# ArduinoZeroV4_0_1.net
KiCad netlist of a schematic drawn in Altium Designer
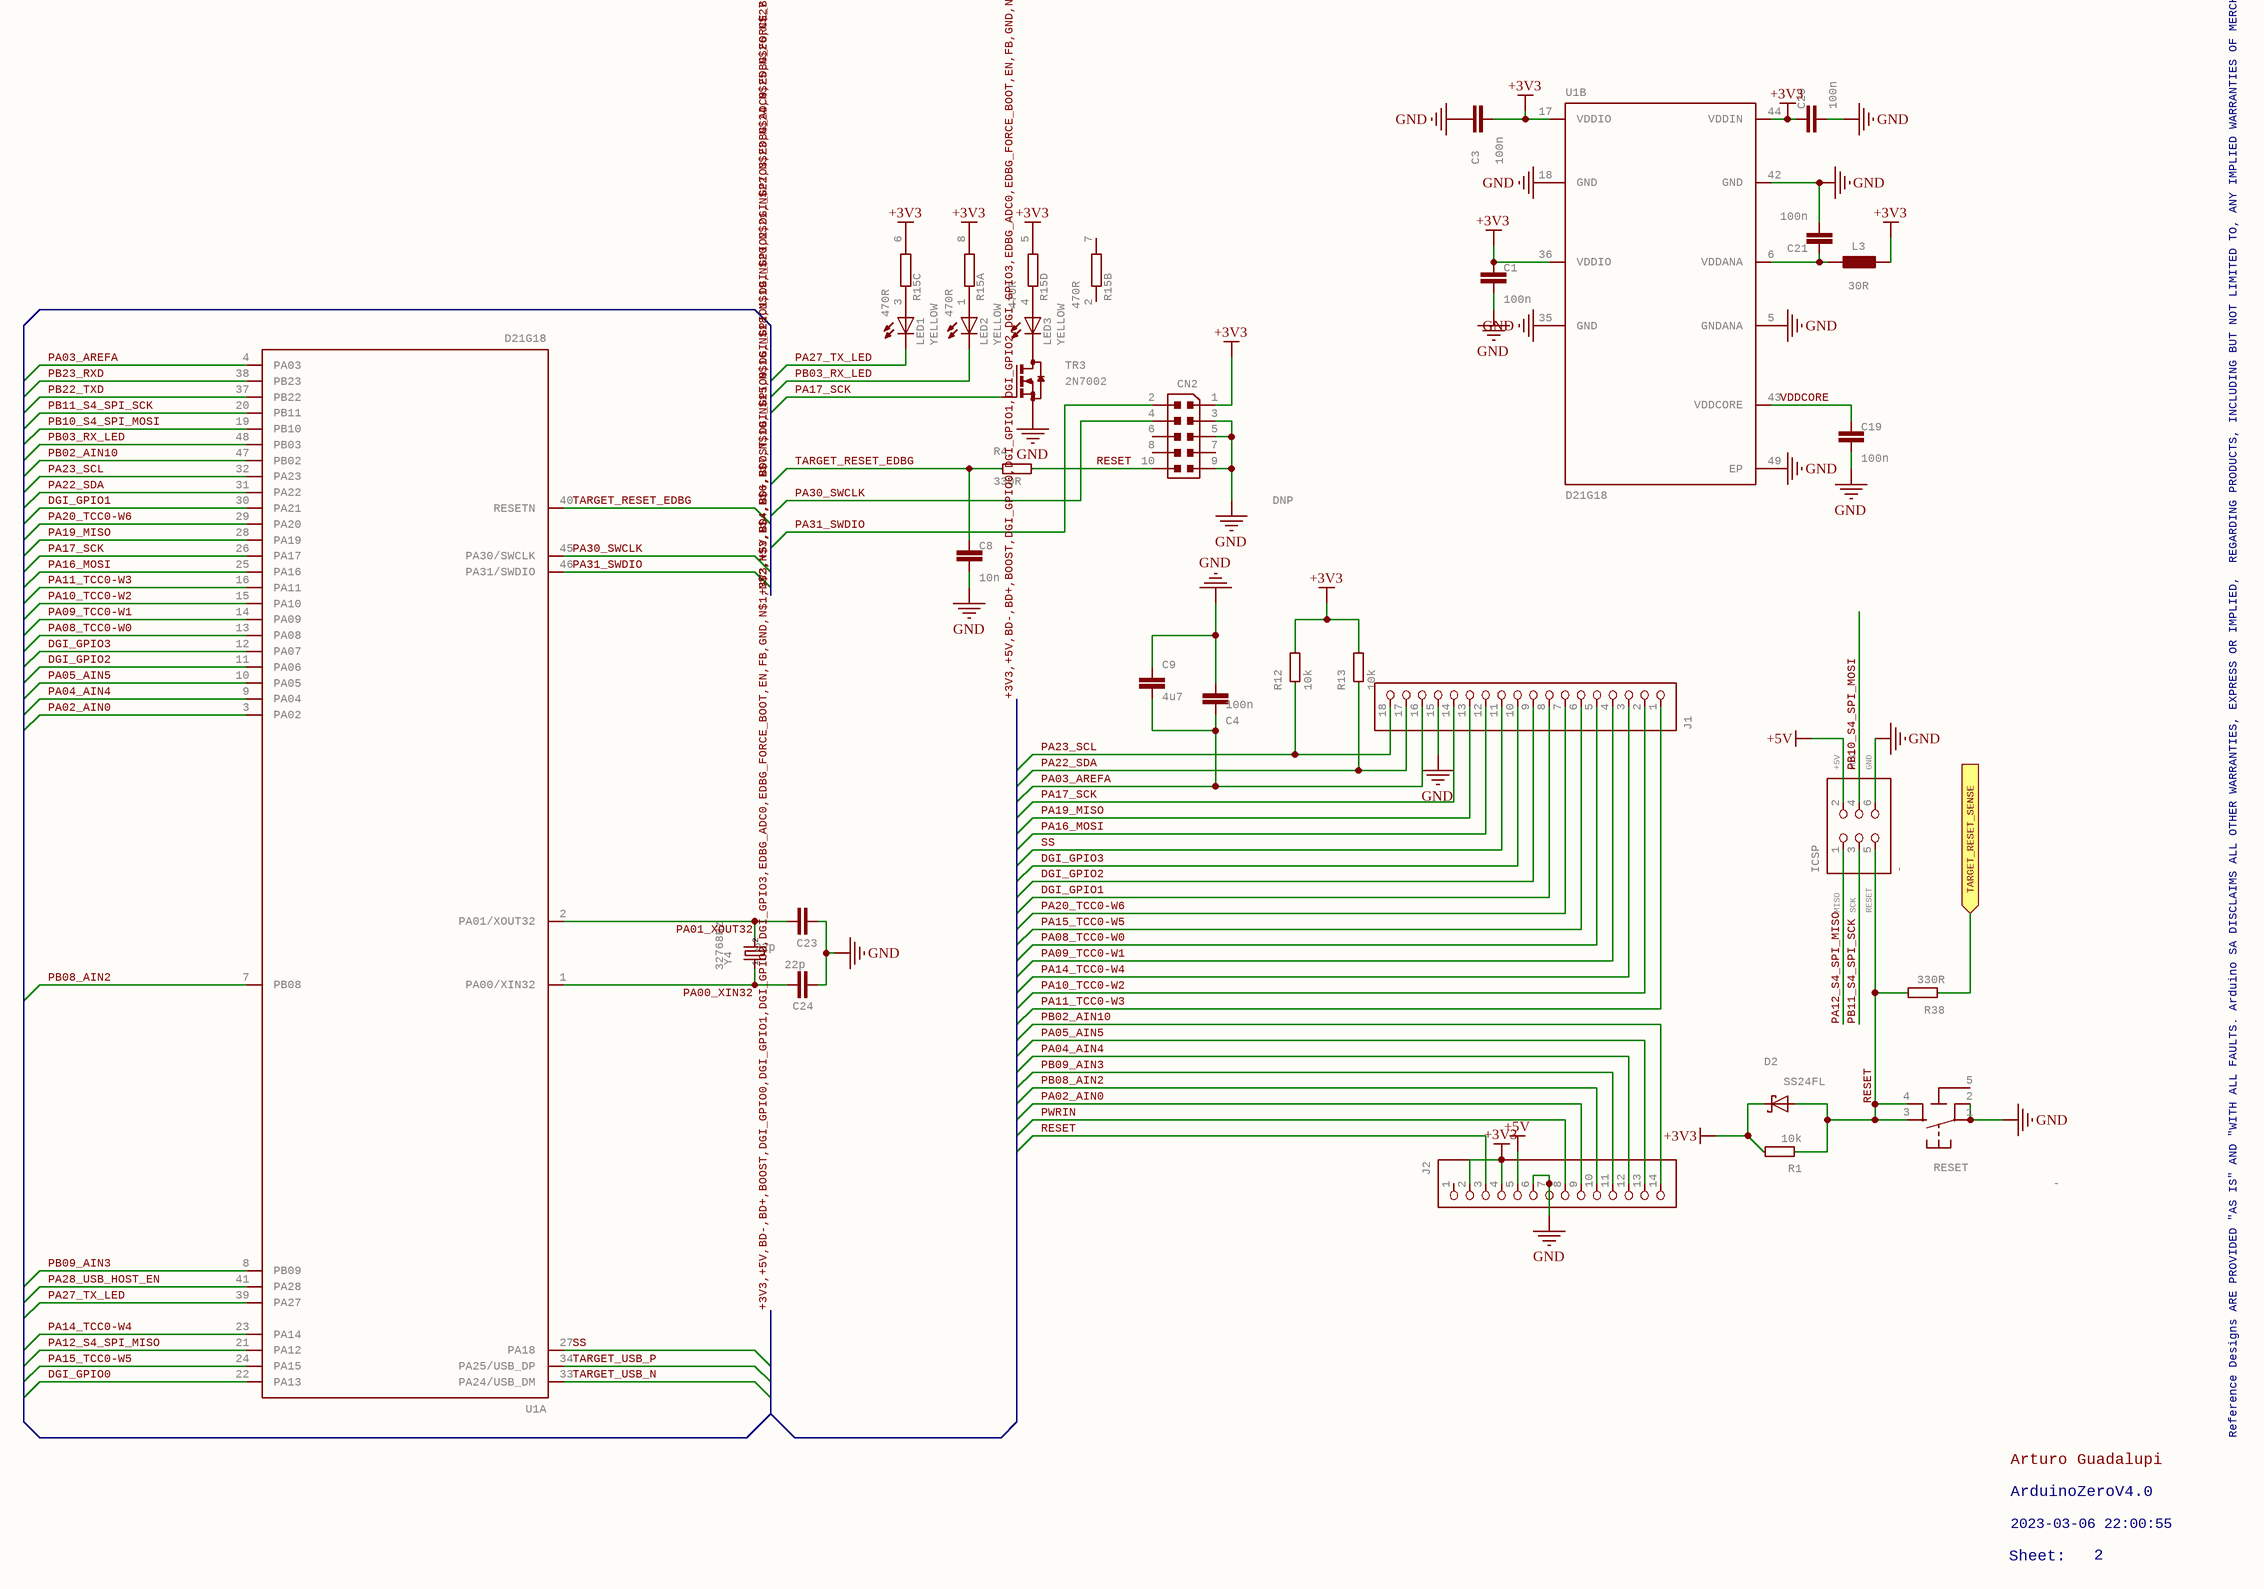
[diagram p0: ArduinoZeroV4.0_1.SchDoc]

(export (version "E")
  (design (tool "Eeschema 10.0.6"))
  (components
    (comp (ref "C1")
      (value "100n")
      (footprint "0603-1608X90N")
      (description "SMD Capacitor")
      (fields (field (name "MANUFACTURER") "Murata"))
      (libsource (lib "") (part "C-0603_1"))
    )
    (comp (ref "C3")
      (value "100n")
      (footprint "0603-1608X90N")
      (description "SMD Capacitor")
      (fields (field (name "MANUFACTURER") "Murata"))
      (libsource (lib "Arduino-rcl") (part "C-0603"))
    )
    (comp (ref "C4")
      (value "100n")
      (footprint "0402-1005X55N")
      (description "SMD Capacitor")
      (fields (field (name "MANUFACTURER") "TDK"))
      (libsource (lib "Arduino-rcl") (part "C-0402"))
    )
    (comp (ref "C8")
      (value "10n")
      (footprint "0603-1608X90N")
      (description "SMD Capacitor")
      (fields (field (name "MANUFACTURER") "Murata"))
      (libsource (lib "") (part "C-0603_1"))
    )
    (comp (ref "C9")
      (value "4u7")
      (footprint "0603-1608X90N")
      (description "SMD Capacitor")
      (fields (field (name "MANUFACTURER") "Murata"))
      (libsource (lib "") (part "C-0603_1"))
    )
    (comp (ref "C19")
      (value "100n")
      (footprint "0603-1608X90N")
      (description "SMD Capacitor")
      (fields (field (name "MANUFACTURER") "Murata"))
      (libsource (lib "") (part "C-0603_1"))
    )
    (comp (ref "C20")
      (value "100n")
      (footprint "0603-1608X90N")
      (description "SMD Capacitor")
      (fields (field (name "MANUFACTURER") "Murata"))
      (libsource (lib "Arduino-rcl") (part "C-0603"))
    )
    (comp (ref "C21")
      (value "100n")
      (footprint "0603-1608X90N")
      (description "SMD Capacitor")
      (fields (field (name "MANUFACTURER") "Murata"))
      (libsource (lib "") (part "C-0603_3"))
    )
    (comp (ref "C23")
      (value "22p")
      (footprint "0603-1608X90N")
      (description "SMD Capacitor")
      (fields (field (name "MANUFACTURER") "Samsung"))
      (libsource (lib "") (part "C-0603_2"))
    )
    (comp (ref "C24")
      (value "22p")
      (footprint "0603-1608X90N")
      (description "SMD Capacitor")
      (fields (field (name "MANUFACTURER") "Samsung"))
      (libsource (lib "") (part "C-0603_2"))
    )
    (comp (ref "CN2")
      (value "DNP")
      (footprint "PINHEAD_2X05_127")
      (description "2x5 PASSO 1,27")
      (libsource (lib "Arduino-connectors") (part "JTAG_CONNECTOR-DNP"))
    )
    (comp (ref "D2")
      (value "SS24FL")
      (footprint "SOD123F")
      (description "Schottky diode")
      (fields (field (name "MANUFACTURER") "Fairchild"))
      (libsource (lib "Arduino-diodes") (part "SS24FL"))
    )
    (comp (ref "ICSP")
      (value "-")
      (footprint "2X03")
      (description "PIN HEADER")
      (fields
        (field (name "MISO") "MISO")
        (field (name "SCK") "SCK")
        (field (name "RESET") "RESET")
        (field (name "+5V") "+5V")
        (field (name "MOSI") "MOSI")
        (field (name "GND") "GND")
        (field (name "MANUFACTURER") "Adam Tech")
      )
      (libsource (lib "Arduino-connectors") (part "PINHD-2X03-ICSPTH"))
    )
    (comp (ref "J1")
      (value "-")
      (footprint "1X18-CUSTOM")
      (description "Pin header")
      (libsource (lib "Arduino-connectors") (part "PINHD-1X18-CUSTOM_OLD"))
    )
    (comp (ref "J2")
      (value "-")
      (footprint "1X14-CUSTOM")
      (description "PIN HEADER")
      (libsource (lib "Arduino-connectors") (part "PINHD-1X14-CUSTOM_OLD"))
    )
    (comp (ref "L3")
      (value "30R")
      (footprint "0805-R2013X50N")
      (description "SMD ferrite")
      (fields (field (name "MANUFACTURER") "Murata"))
      (libsource (lib "Arduino-rcl") (part "FERRITE0805"))
    )
    (comp (ref "LED1")
      (value "YELLOW")
      (footprint "CHIPLED_0805")
      (description "LED")
      (fields (field (name "MANUFACTURER") "Lite-On"))
      (libsource (lib "Arduino-diodes") (part "LED-0805"))
    )
    (comp (ref "LED2")
      (value "YELLOW")
      (footprint "CHIPLED_0805")
      (description "LED")
      (fields (field (name "MANUFACTURER") "Lite-On"))
      (libsource (lib "Arduino-diodes") (part "LED-0805"))
    )
    (comp (ref "LED3")
      (value "YELLOW")
      (footprint "CHIPLED_0805")
      (description "LED")
      (fields (field (name "MANUFACTURER") "Lite-On"))
      (libsource (lib "Arduino-diodes") (part "LED-0805"))
    )
    (comp (ref "R1")
      (value "10k")
      (footprint "C0603")
      (description "SMD Resistor")
      (fields (field (name "MANUFACTURER") "Yageo"))
      (libsource (lib "Arduino-rcl") (part "R-0603"))
    )
    (comp (ref "R4")
      (value "330R")
      (footprint "C0603")
      (description "SMD Resistor")
      (fields (field (name "MANUFACTURER") "Yageo"))
      (libsource (lib "Arduino-rcl") (part "R-0603"))
    )
    (comp (ref "R12")
      (value "10k")
      (footprint "C0603")
      (description "SMD Resistor")
      (fields (field (name "MANUFACTURER") "Yageo"))
      (libsource (lib "Arduino-rcl") (part "R-0603"))
    )
    (comp (ref "R13")
      (value "10k")
      (footprint "C0603")
      (description "SMD Resistor")
      (fields (field (name "MANUFACTURER") "Yageo"))
      (libsource (lib "Arduino-rcl") (part "R-0603"))
    )
    (comp (ref "R15")
      (value "470R")
      (footprint "CAY16")
      (description "Array Chip Resistor   Source: RS Component / Phycomp")
      (fields (field (name "MANUFACTURER") "Bourns Inc."))
      (libsource (lib "Arduino-rcl") (part "4R-NCAY16"))
    )
    (comp (ref "R38")
      (value "330R")
      (footprint "C0603")
      (description "SMD Resistor")
      (fields (field (name "MANUFACTURER") "Yageo"))
      (libsource (lib "Arduino-rcl") (part "R-0603"))
    )
    (comp (ref "RESET")
      (value "-")
      (footprint "TS42")
      (description "Pushbutton")
      (fields (field (name "MANUFACTURER") "TE") (field (name "LIBRARYNAME") "Arduino-pushbuttons"))
      (libsource (lib "Arduino-pushbuttons") (part "TACTILE2"))
    )
    (comp (ref "TR3")
      (value "2N7002")
      (footprint "SOT23")
      (description "MOSFET N-CH 60V 115MA")
      (fields (field (name "MANUFACTURER") "Micro Commercial Co"))
      (libsource (lib "Arduino-transistors") (part "2N7002T-SOT23"))
    )
    (comp (ref "U1")
      (value "D21G18")
      (footprint "QFN50P700X700X90-49XN-EPSQ515")
      (description "ARMÂ® CortexÂ®-M0+ SAM D21G Microcontroller IC 32-Bit 48MHz 256KB (256K x 8) FLASH 48-TQFP (7x7)")
      (fields (field (name "MANUFACTURER") "DNP") (field (name "LIBRARYNAME") "Arduino-ucs&SoCs"))
      (libsource (lib "Arduino-ucs&SoCs") (part "ATSAMD21G18A-48QFN"))
    )
    (comp (ref "Y4")
      (value "32768Hz")
      (footprint "ABS07")
      (description "LF crystal")
      (fields (field (name "1") "1") (field (name "2") "2") (field (name "MANUFACTURER") "Abracon LLC"))
      (libsource (lib "Arduino-crystals") (part "32.768KHZ"))
    )
  )
  (nets
    (net (code "2") (name "+3V3") (class "Default")
      (node (ref "C1") (pin "1") (pinfunction "1_1") (pintype "passive"))
      (node (ref "C20") (pin "1") (pinfunction "1_1") (pintype "passive"))
      (node (ref "C3") (pin "2") (pinfunction "2_2") (pintype "passive"))
      (node (ref "CN2") (pin "1") (pinfunction "1_1") (pintype "passive"))
      (node (ref "D2") (pin "C") (pinfunction "C_C") (pintype "passive"))
      (node (ref "J2") (pin "2") (pinfunction "2_2") (pintype "passive"))
      (node (ref "J2") (pin "4") (pinfunction "4_4") (pintype "passive"))
      (node (ref "L3") (pin "2") (pinfunction "2_2") (pintype "passive"))
      (node (ref "R1") (pin "2") (pinfunction "2_2") (pintype "passive"))
      (node (ref "R12") (pin "2") (pinfunction "2_2") (pintype "passive"))
      (node (ref "R13") (pin "2") (pinfunction "2_2") (pintype "passive"))
      (node (ref "R15") (pin "5") (pinfunction "2_5") (pintype "passive"))
      (node (ref "R15") (pin "6") (pinfunction "2_6") (pintype "passive"))
      (node (ref "R15") (pin "8") (pinfunction "2_8") (pintype "passive"))
      (node (ref "U1") (pin "17") (pinfunction "VDDIO_17") (pintype "power_in"))
      (node (ref "U1") (pin "36") (pinfunction "VDDIO_36") (pintype "power_in"))
      (node (ref "U1") (pin "44") (pinfunction "VDDIN_44") (pintype "power_in"))
    )
    (net (code "3") (name "+5V") (class "Default")
      (node (ref "ICSP") (pin "2") (pinfunction "2_2") (pintype "passive"))
      (node (ref "J2") (pin "5") (pinfunction "5_5") (pintype "passive"))
    )
    (net (code "4") (name "/DGI_GPIO0") (class "Default")
      (node (ref "U1") (pin "22") (pinfunction "PA13_22") (pintype "bidirectional"))
    )
    (net (code "5") (name "/DGI_GPIO1") (class "Default")
      (node (ref "J1") (pin "8") (pinfunction "8_8") (pintype "passive"))
      (node (ref "U1") (pin "30") (pinfunction "PA21_30") (pintype "bidirectional"))
    )
    (net (code "6") (name "/DGI_GPIO2") (class "Default")
      (node (ref "J1") (pin "9") (pinfunction "9_9") (pintype "passive"))
      (node (ref "U1") (pin "11") (pinfunction "PA06_11") (pintype "bidirectional"))
    )
    (net (code "7") (name "/DGI_GPIO3") (class "Default")
      (node (ref "J1") (pin "10") (pinfunction "10_10") (pintype "passive"))
      (node (ref "U1") (pin "12") (pinfunction "PA07_12") (pintype "bidirectional"))
    )
    (net (code "8") (name "/PA00_XIN32") (class "Default")
      (node (ref "C24") (pin "2") (pinfunction "2_2") (pintype "passive"))
      (node (ref "U1") (pin "1") (pinfunction "PA00/XIN32_1") (pintype "bidirectional"))
      (node (ref "Y4") (pin "1") (pinfunction "1_1") (pintype "passive"))
    )
    (net (code "9") (name "/PA01_XOUT32") (class "Default")
      (node (ref "C23") (pin "2") (pinfunction "2_2") (pintype "passive"))
      (node (ref "U1") (pin "2") (pinfunction "PA01/XOUT32_2") (pintype "bidirectional"))
      (node (ref "Y4") (pin "2") (pinfunction "2_2") (pintype "passive"))
    )
    (net (code "10") (name "/PA02_AIN0") (class "Default")
      (node (ref "J2") (pin "9") (pinfunction "9_9") (pintype "passive"))
      (node (ref "U1") (pin "3") (pinfunction "PA02_3") (pintype "bidirectional"))
    )
    (net (code "11") (name "/PA03_AREFA") (class "Default")
      (node (ref "C4") (pin "1") (pinfunction "1_1") (pintype "passive"))
      (node (ref "C9") (pin "2") (pinfunction "2_2") (pintype "passive"))
      (node (ref "J1") (pin "16") (pinfunction "16_16") (pintype "passive"))
      (node (ref "U1") (pin "4") (pinfunction "PA03_4") (pintype "bidirectional"))
    )
    (net (code "12") (name "/PA04_AIN4") (class "Default")
      (node (ref "J2") (pin "12") (pinfunction "12_12") (pintype "passive"))
      (node (ref "U1") (pin "9") (pinfunction "PA04_9") (pintype "bidirectional"))
    )
    (net (code "13") (name "/PA05_AIN5") (class "Default")
      (node (ref "J2") (pin "13") (pinfunction "13_13") (pintype "passive"))
      (node (ref "U1") (pin "10") (pinfunction "PA05_10") (pintype "bidirectional"))
    )
    (net (code "14") (name "/PA08_TCC0-W0") (class "Default")
      (node (ref "J1") (pin "5") (pinfunction "5_5") (pintype "passive"))
      (node (ref "U1") (pin "13") (pinfunction "PA08_13") (pintype "bidirectional"))
    )
    (net (code "15") (name "/PA09_TCC0-W1") (class "Default")
      (node (ref "J1") (pin "4") (pinfunction "4_4") (pintype "passive"))
      (node (ref "U1") (pin "14") (pinfunction "PA09_14") (pintype "bidirectional"))
    )
    (net (code "16") (name "/PA10_TCC0-W2") (class "Default")
      (node (ref "J1") (pin "2") (pinfunction "2_2") (pintype "passive"))
      (node (ref "U1") (pin "15") (pinfunction "PA10_15") (pintype "bidirectional"))
    )
    (net (code "17") (name "/PA11_TCC0-W3") (class "Default")
      (node (ref "J1") (pin "1") (pinfunction "1_1") (pintype "passive"))
      (node (ref "U1") (pin "16") (pinfunction "PA11_16") (pintype "bidirectional"))
    )
    (net (code "18") (name "/PA12_S4_SPI_MISO") (class "Default")
      (node (ref "ICSP") (pin "1") (pinfunction "1_1") (pintype "passive"))
      (node (ref "U1") (pin "21") (pinfunction "PA12_21") (pintype "bidirectional"))
    )
    (net (code "19") (name "/PA14_TCC0-W4") (class "Default")
      (node (ref "J1") (pin "3") (pinfunction "3_3") (pintype "passive"))
      (node (ref "U1") (pin "23") (pinfunction "PA14_23") (pintype "bidirectional"))
    )
    (net (code "20") (name "/PA15_TCC0-W5") (class "Default")
      (node (ref "J1") (pin "6") (pinfunction "6_6") (pintype "passive"))
      (node (ref "U1") (pin "24") (pinfunction "PA15_24") (pintype "bidirectional"))
    )
    (net (code "21") (name "/PA16_MOSI") (class "Default")
      (node (ref "J1") (pin "12") (pinfunction "12_12") (pintype "passive"))
      (node (ref "U1") (pin "25") (pinfunction "PA16_25") (pintype "bidirectional"))
    )
    (net (code "22") (name "/PA17_SCK") (class "Default")
      (node (ref "J1") (pin "14") (pinfunction "14_14") (pintype "passive"))
      (node (ref "TR3") (pin "1") (pinfunction "G_1") (pintype "passive"))
      (node (ref "U1") (pin "26") (pinfunction "PA17_26") (pintype "bidirectional"))
    )
    (net (code "23") (name "/PA19_MISO") (class "Default")
      (node (ref "J1") (pin "13") (pinfunction "13_13") (pintype "passive"))
      (node (ref "U1") (pin "28") (pinfunction "PA19_28") (pintype "bidirectional"))
    )
    (net (code "24") (name "/PA20_TCC0-W6") (class "Default")
      (node (ref "J1") (pin "7") (pinfunction "7_7") (pintype "passive"))
      (node (ref "U1") (pin "29") (pinfunction "PA20_29") (pintype "bidirectional"))
    )
    (net (code "25") (name "/PA22_SDA") (class "Default")
      (node (ref "J1") (pin "17") (pinfunction "17_17") (pintype "passive"))
      (node (ref "R13") (pin "1") (pinfunction "1_1") (pintype "passive"))
      (node (ref "U1") (pin "31") (pinfunction "PA22_31") (pintype "bidirectional"))
    )
    (net (code "26") (name "/PA23_SCL") (class "Default")
      (node (ref "J1") (pin "18") (pinfunction "18_18") (pintype "passive"))
      (node (ref "R12") (pin "1") (pinfunction "1_1") (pintype "passive"))
      (node (ref "U1") (pin "32") (pinfunction "PA23_32") (pintype "bidirectional"))
    )
    (net (code "27") (name "/PA27_TX_LED") (class "Default")
      (node (ref "LED1") (pin "C") (pinfunction "C_C") (pintype "passive"))
      (node (ref "U1") (pin "39") (pinfunction "PA27_39") (pintype "bidirectional"))
    )
    (net (code "28") (name "/PA28_USB_HOST_EN") (class "Default")
      (node (ref "U1") (pin "41") (pinfunction "PA28_41") (pintype "bidirectional"))
    )
    (net (code "29") (name "/PA30_SWCLK") (class "Default")
      (node (ref "CN2") (pin "4") (pinfunction "4_4") (pintype "passive"))
      (node (ref "U1") (pin "45") (pinfunction "PA30/SWCLK_45") (pintype "bidirectional"))
    )
    (net (code "30") (name "/PA31_SWDIO") (class "Default")
      (node (ref "CN2") (pin "2") (pinfunction "2_2") (pintype "passive"))
      (node (ref "U1") (pin "46") (pinfunction "PA31/SWDIO_46") (pintype "bidirectional"))
    )
    (net (code "31") (name "/PB02_AIN10") (class "Default")
      (node (ref "J2") (pin "14") (pinfunction "14_14") (pintype "passive"))
      (node (ref "U1") (pin "47") (pinfunction "PB02_47") (pintype "bidirectional"))
    )
    (net (code "32") (name "/PB03_RX_LED") (class "Default")
      (node (ref "LED2") (pin "C") (pinfunction "C_C") (pintype "passive"))
      (node (ref "U1") (pin "48") (pinfunction "PB03_48") (pintype "bidirectional"))
    )
    (net (code "33") (name "/PB08_AIN2") (class "Default")
      (node (ref "J2") (pin "10") (pinfunction "10_10") (pintype "passive"))
      (node (ref "U1") (pin "7") (pinfunction "PB08_7") (pintype "bidirectional"))
    )
    (net (code "34") (name "/PB09_AIN3") (class "Default")
      (node (ref "J2") (pin "11") (pinfunction "11_11") (pintype "passive"))
      (node (ref "U1") (pin "8") (pinfunction "PB09_8") (pintype "bidirectional"))
    )
    (net (code "35") (name "/PB10_S4_SPI_MOSI") (class "Default")
      (node (ref "ICSP") (pin "4") (pinfunction "4_4") (pintype "passive"))
      (node (ref "U1") (pin "19") (pinfunction "PB10_19") (pintype "bidirectional"))
    )
    (net (code "36") (name "/PB11_S4_SPI_SCK") (class "Default")
      (node (ref "ICSP") (pin "3") (pinfunction "3_3") (pintype "passive"))
      (node (ref "U1") (pin "20") (pinfunction "PB11_20") (pintype "bidirectional"))
    )
    (net (code "37") (name "/PB22_TXD") (class "Default")
      (node (ref "U1") (pin "37") (pinfunction "PB22_37") (pintype "bidirectional"))
    )
    (net (code "38") (name "/PB23_RXD") (class "Default")
      (node (ref "U1") (pin "38") (pinfunction "PB23_38") (pintype "bidirectional"))
    )
    (net (code "39") (name "/PWRIN") (class "Default")
      (node (ref "J2") (pin "8") (pinfunction "8_8") (pintype "passive"))
    )
    (net (code "40") (name "/RESET") (class "Default")
      (node (ref "CN2") (pin "10") (pinfunction "10_10") (pintype "passive"))
      (node (ref "D2") (pin "A") (pinfunction "A_A") (pintype "passive"))
      (node (ref "ICSP") (pin "5") (pinfunction "5_5") (pintype "passive"))
      (node (ref "J2") (pin "3") (pinfunction "3_3") (pintype "passive"))
      (node (ref "R1") (pin "1") (pinfunction "1_1") (pintype "passive"))
      (node (ref "R38") (pin "2") (pinfunction "2_2") (pintype "passive"))
      (node (ref "R4") (pin "2") (pinfunction "2_2") (pintype "passive"))
      (node (ref "RESET") (pin "3") (pinfunction "3_3") (pintype "passive"))
      (node (ref "RESET") (pin "4") (pinfunction "4_4") (pintype "passive"))
    )
    (net (code "41") (name "/SS") (class "Default")
      (node (ref "J1") (pin "11") (pinfunction "11_11") (pintype "passive"))
      (node (ref "U1") (pin "27") (pinfunction "PA18_27") (pintype "bidirectional"))
    )
    (net (code "42") (name "/TARGET_RESET_EDBG") (class "Default")
      (node (ref "C8") (pin "1") (pinfunction "1_1") (pintype "passive"))
      (node (ref "R4") (pin "1") (pinfunction "1_1") (pintype "passive"))
      (node (ref "U1") (pin "40") (pinfunction "RESETN_40") (pintype "bidirectional"))
    )
    (net (code "43") (name "/TARGET_RESET_SENSE") (class "Default")
      (node (ref "R38") (pin "1") (pinfunction "1_1") (pintype "passive"))
    )
    (net (code "44") (name "/TARGET_USB_N") (class "Default")
      (node (ref "U1") (pin "33") (pinfunction "PA24/USB_DM_33") (pintype "bidirectional"))
    )
    (net (code "45") (name "/TARGET_USB_P") (class "Default")
      (node (ref "U1") (pin "34") (pinfunction "PA25/USB_DP_34") (pintype "bidirectional"))
    )
    (net (code "46") (name "/VDDCORE") (class "Default")
      (node (ref "C19") (pin "1") (pinfunction "1_1") (pintype "passive"))
      (node (ref "U1") (pin "43") (pinfunction "VDDCORE_43") (pintype "power_in"))
    )
    (net (code "48") (name "GND") (class "Default")
      (node (ref "C1") (pin "2") (pinfunction "2_2") (pintype "passive"))
      (node (ref "C19") (pin "2") (pinfunction "2_2") (pintype "passive"))
      (node (ref "C20") (pin "2") (pinfunction "2_2") (pintype "passive"))
      (node (ref "C21") (pin "2") (pinfunction "2_2") (pintype "passive"))
      (node (ref "C23") (pin "1") (pinfunction "1_1") (pintype "passive"))
      (node (ref "C24") (pin "1") (pinfunction "1_1") (pintype "passive"))
      (node (ref "C3") (pin "1") (pinfunction "1_1") (pintype "passive"))
      (node (ref "C4") (pin "2") (pinfunction "2_2") (pintype "passive"))
      (node (ref "C8") (pin "2") (pinfunction "2_2") (pintype "passive"))
      (node (ref "C9") (pin "1") (pinfunction "1_1") (pintype "passive"))
      (node (ref "CN2") (pin "3") (pinfunction "3_3") (pintype "passive"))
      (node (ref "CN2") (pin "5") (pinfunction "5_5") (pintype "passive"))
      (node (ref "CN2") (pin "9") (pinfunction "9_9") (pintype "passive"))
      (node (ref "ICSP") (pin "6") (pinfunction "6_6") (pintype "passive"))
      (node (ref "J1") (pin "15") (pinfunction "15_15") (pintype "passive"))
      (node (ref "J2") (pin "6") (pinfunction "6_6") (pintype "passive"))
      (node (ref "J2") (pin "7") (pinfunction "7_7") (pintype "passive"))
      (node (ref "RESET") (pin "1") (pinfunction "1_1") (pintype "passive"))
      (node (ref "RESET") (pin "2") (pinfunction "2_2") (pintype "passive"))
      (node (ref "TR3") (pin "2") (pinfunction "S_2") (pintype "passive"))
      (node (ref "U1") (pin "18") (pinfunction "GND_18") (pintype "power_in"))
      (node (ref "U1") (pin "35") (pinfunction "GND_35") (pintype "power_in"))
      (node (ref "U1") (pin "42") (pinfunction "GND_42") (pintype "power_in"))
      (node (ref "U1") (pin "49") (pinfunction "EP_49") (pintype "passive"))
      (node (ref "U1") (pin "5") (pinfunction "GNDANA_5") (pintype "power_in"))
    )
    (net (code "49") (name "Net-(LED2-PadA)") (class "Default")
      (node (ref "LED2") (pin "A") (pinfunction "A_A") (pintype "passive"))
      (node (ref "R15") (pin "1") (pinfunction "1_1") (pintype "passive"))
    )
    (net (code "50") (name "Net-(R15C-1)") (class "Default")
      (node (ref "LED1") (pin "A") (pinfunction "A_A") (pintype "passive"))
      (node (ref "R15") (pin "3") (pinfunction "1_3") (pintype "passive"))
    )
    (net (code "51") (name "Net-(R15D-1)") (class "Default")
      (node (ref "LED3") (pin "A") (pinfunction "A_A") (pintype "passive"))
      (node (ref "R15") (pin "4") (pinfunction "1_4") (pintype "passive"))
    )
    (net (code "52") (name "Net-(TR3-D)") (class "Default")
      (node (ref "LED3") (pin "C") (pinfunction "C_C") (pintype "passive"))
      (node (ref "TR3") (pin "3") (pinfunction "D_3") (pintype "passive"))
    )
    (net (code "53") (name "Net-(U1B-VDDANA)") (class "Default")
      (node (ref "C21") (pin "1") (pinfunction "1_1") (pintype "passive"))
      (node (ref "L3") (pin "1") (pinfunction "1_1") (pintype "passive"))
      (node (ref "U1") (pin "6") (pinfunction "VDDANA_6") (pintype "power_in"))
    )
    (net (code "54") (name "unconnected-(CN2-Pad6)") (class "Default")
      (node (ref "CN2") (pin "6") (pinfunction "6_6") (pintype "passive"))
    )
    (net (code "55") (name "unconnected-(CN2-Pad7)") (class "Default")
      (node (ref "CN2") (pin "7") (pinfunction "7_7") (pintype "passive"))
    )
    (net (code "56") (name "unconnected-(CN2-Pad8)") (class "Default")
      (node (ref "CN2") (pin "8") (pinfunction "8_8") (pintype "passive"))
    )
    (net (code "57") (name "unconnected-(J2-Pad1)") (class "Default")
      (node (ref "J2") (pin "1") (pinfunction "1_1") (pintype "passive"))
    )
    (net (code "58") (name "unconnected-(R15B-1-Pad2)") (class "Default")
      (node (ref "R15") (pin "2") (pinfunction "1_2") (pintype "passive"))
    )
    (net (code "59") (name "unconnected-(R15B-2-Pad7)") (class "Default")
      (node (ref "R15") (pin "7") (pinfunction "2_7") (pintype "passive"))
    )
    (net (code "60") (name "unconnected-(RESET-5-GND-Pad5)") (class "Default")
      (node (ref "RESET") (pin "5") (pinfunction "5-GND_5") (pintype "power_in"))
    )
  )
)
